# vusbtinyisp_smt.net
KiCad netlist of a schematic drawn in EAGLE
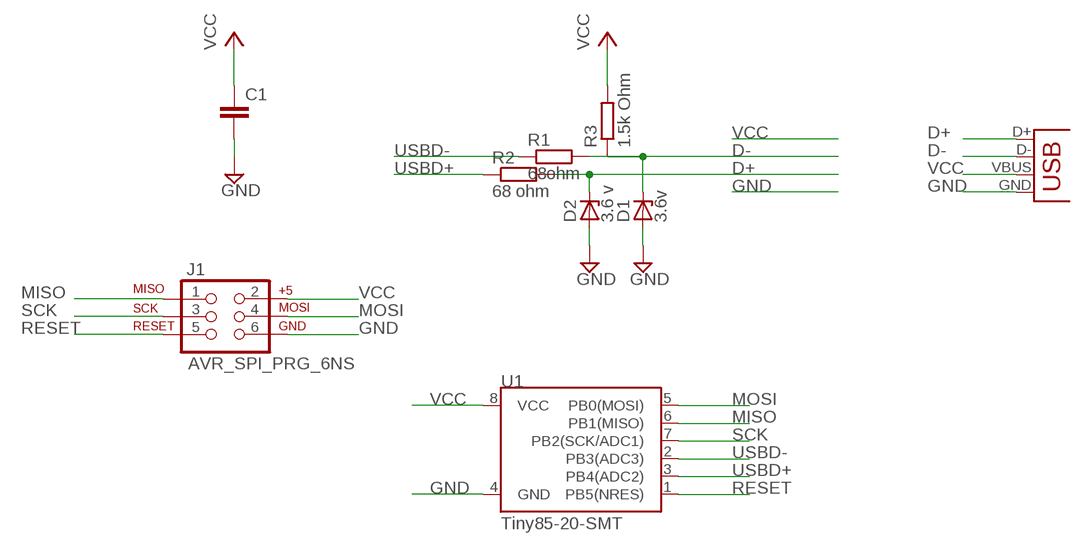
[diagram p0: schematic, sheet 1]

(export (version "E")
  (design (tool "Eeschema 10.0.6"))
  (components
    (comp (ref "C1")
      (value "CAP1206")
      (footprint "eagle-import:1206")
      (libsource (lib "eagle-import") (part "CAP1206"))
    )
    (comp (ref "D1")
      (value "3.6v")
      (footprint "eagle-import:SOT23")
      (libsource (lib "eagle-import") (part "ZENER-DIODESOT23"))
    )
    (comp (ref "D2")
      (value "3.6 v")
      (footprint "eagle-import:SOT23")
      (libsource (lib "eagle-import") (part "ZENER-DIODESOT23"))
    )
    (comp (ref "J1")
      (value "AVR_SPI_PRG_6NS")
      (footprint "eagle-import:2X3-NS")
      (libsource (lib "eagle-import") (part "AVR_SPI_PRG_6NS"))
    )
    (comp (ref "JP2")
      (value "USBSMD")
      (footprint "eagle-import:USB-MINIB")
      (libsource (lib "eagle-import") (part "USBSMD"))
    )
    (comp (ref "R1")
      (value "68ohm")
      (footprint "eagle-import:R0805")
      (libsource (lib "eagle-import") (part "R-EU_R0805"))
    )
    (comp (ref "R2")
      (value "68 ohm")
      (footprint "eagle-import:R0805")
      (libsource (lib "eagle-import") (part "R-EU_R0805"))
    )
    (comp (ref "R3")
      (value "1.5k Ohm")
      (footprint "eagle-import:R1206")
      (libsource (lib "eagle-import") (part "R-EU_R1206"))
    )
    (comp (ref "U1")
      (value "Tiny85-20-SMT")
      (footprint "eagle-import:SO08-EIAJ")
      (libsource (lib "eagle-import") (part "ATTINY45TINY85-20-SMT"))
    )
  )
  (nets
    (net (code "1") (name "/D+") (class "Default")
      (node (ref "D2") (pin "3") (pinfunction "C_3") (pintype "passive"))
      (node (ref "JP2") (pin "D+") (pinfunction "D+_D+") (pintype "bidirectional"))
      (node (ref "R2") (pin "2") (pinfunction "2_2") (pintype "passive"))
    )
    (net (code "2") (name "/D-") (class "Default")
      (node (ref "D1") (pin "3") (pinfunction "C_3") (pintype "passive"))
      (node (ref "JP2") (pin "D-") (pinfunction "D-_D-") (pintype "bidirectional"))
      (node (ref "R1") (pin "2") (pinfunction "2_2") (pintype "passive"))
      (node (ref "R3") (pin "1") (pinfunction "1_1") (pintype "passive"))
    )
    (net (code "3") (name "/MISO") (class "Default")
      (node (ref "J1") (pin "1") (pinfunction "1_1") (pintype "passive"))
      (node (ref "U1") (pin "6") (pinfunction "PB1(MISO)_6") (pintype "bidirectional"))
    )
    (net (code "4") (name "/MOSI") (class "Default")
      (node (ref "J1") (pin "4") (pinfunction "4_4") (pintype "passive"))
      (node (ref "U1") (pin "5") (pinfunction "PB0(MOSI)_5") (pintype "bidirectional"))
    )
    (net (code "5") (name "/RESET") (class "Default")
      (node (ref "J1") (pin "5") (pinfunction "5_5") (pintype "passive"))
      (node (ref "U1") (pin "1") (pinfunction "PB5(NRES)_1") (pintype "bidirectional"))
    )
    (net (code "6") (name "/SCK") (class "Default")
      (node (ref "J1") (pin "3") (pinfunction "3_3") (pintype "passive"))
      (node (ref "U1") (pin "7") (pinfunction "PB2(SCK/ADC1)_7") (pintype "bidirectional"))
    )
    (net (code "7") (name "/USBD+") (class "Default")
      (node (ref "R2") (pin "1") (pinfunction "1_1") (pintype "passive"))
      (node (ref "U1") (pin "3") (pinfunction "PB4(ADC2)_3") (pintype "bidirectional"))
    )
    (net (code "8") (name "/USBD-") (class "Default")
      (node (ref "R1") (pin "1") (pinfunction "1_1") (pintype "passive"))
      (node (ref "U1") (pin "2") (pinfunction "PB3(ADC3)_2") (pintype "bidirectional"))
    )
    (net (code "9") (name "GND") (class "Default")
      (node (ref "C1") (pin "2") (pinfunction "2_2") (pintype "passive"))
      (node (ref "D1") (pin "1") (pinfunction "A_1") (pintype "passive"))
      (node (ref "D2") (pin "1") (pinfunction "A_1") (pintype "passive"))
      (node (ref "J1") (pin "6") (pinfunction "6_6") (pintype "passive"))
      (node (ref "JP2") (pin "GND") (pinfunction "GND_GND") (pintype "bidirectional"))
      (node (ref "U1") (pin "4") (pinfunction "GND_4") (pintype "bidirectional"))
    )
    (net (code "10") (name "VCC") (class "Default")
      (node (ref "C1") (pin "1") (pinfunction "1_1") (pintype "passive"))
      (node (ref "J1") (pin "2") (pinfunction "2_2") (pintype "passive"))
      (node (ref "JP2") (pin "VBUS") (pinfunction "VBUS_VBUS") (pintype "bidirectional"))
      (node (ref "R3") (pin "2") (pinfunction "2_2") (pintype "passive"))
      (node (ref "U1") (pin "8") (pinfunction "VCC_8") (pintype "bidirectional"))
    )
  )
)
